# SSBSMINI_THROUGHHOLE.net
KiCad netlist of a schematic drawn in EAGLE
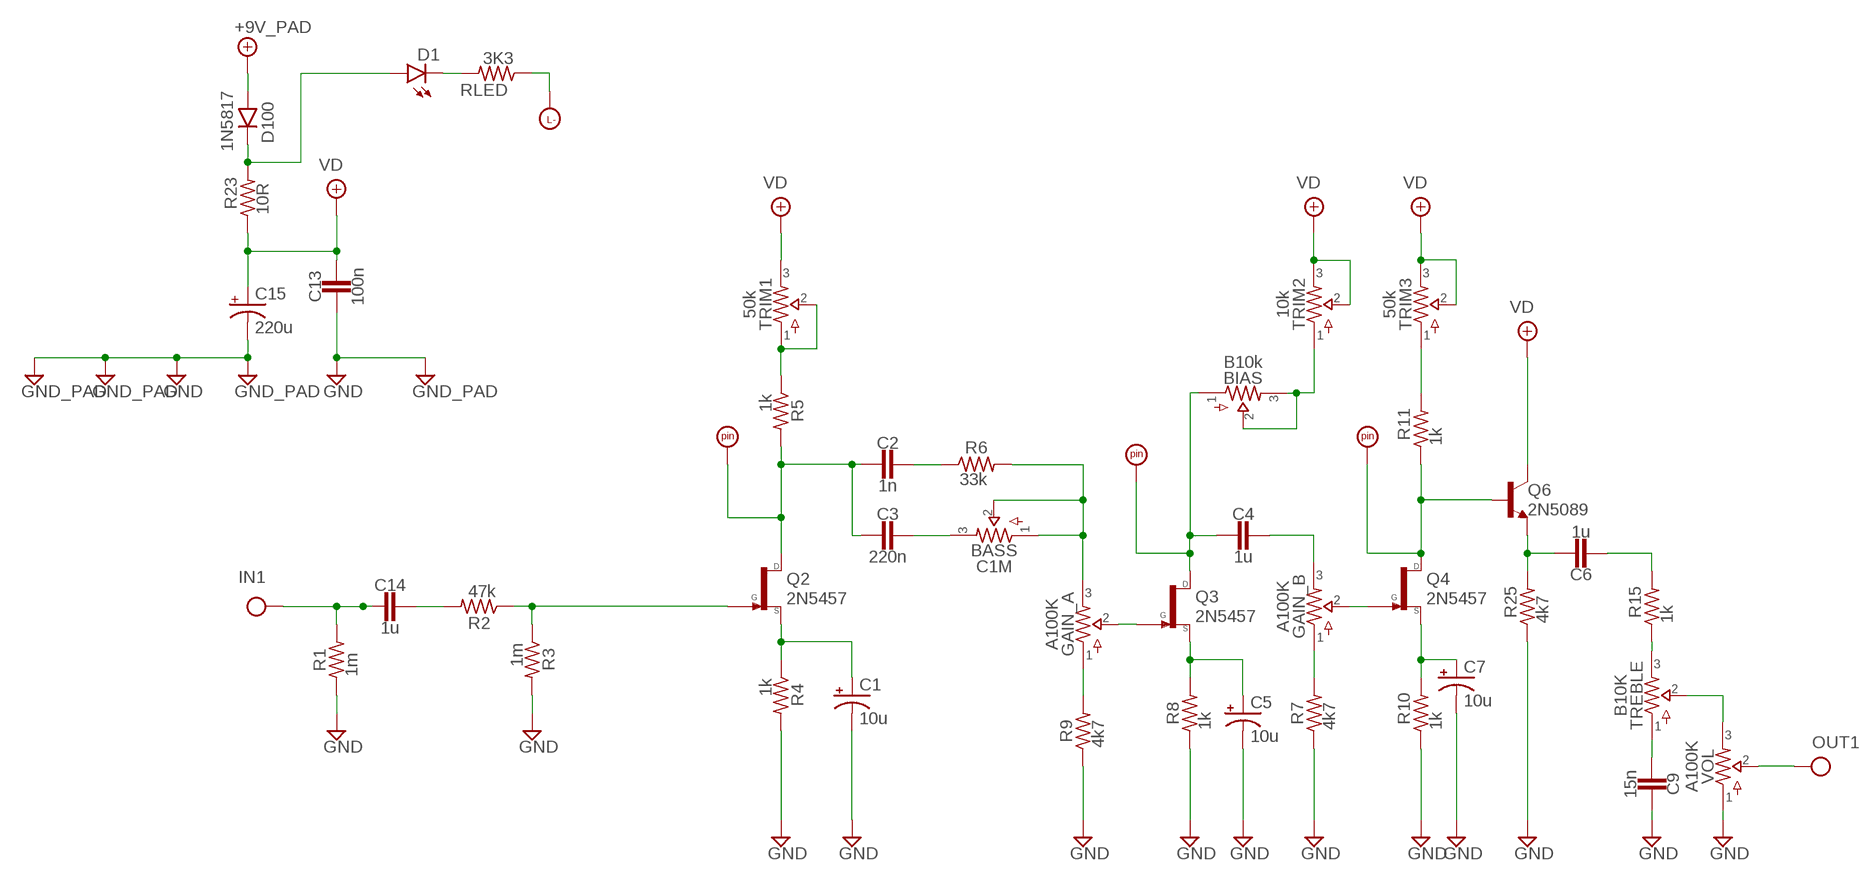
[diagram p0: schematic, sheet 1]

(export (version "E")
  (design (tool "Eeschema 10.0.6"))
  (components
    (comp (ref "BASS")
      (value "C1M")
      (footprint "eagle-import:16MM_B.MOUNT")
      (libsource (lib "eagle-import") (part "16MM.1"))
    )
    (comp (ref "BIAS")
      (value "B10k")
      (footprint "eagle-import:16MM_B.MOUNT")
      (libsource (lib "eagle-import") (part "16MM.1"))
    )
    (comp (ref "C1")
      (value "10u")
      (footprint "eagle-import:050_020_1")
      (libsource (lib "eagle-import") (part "0501"))
    )
    (comp (ref "C2")
      (value "1n")
      (footprint "eagle-import:0.2_.SML")
      (libsource (lib "eagle-import") (part "CAP.2"))
    )
    (comp (ref "C3")
      (value "220n")
      (footprint "eagle-import:0.2_.MED")
      (libsource (lib "eagle-import") (part "CAP.3"))
    )
    (comp (ref "C4")
      (value "1u")
      (footprint "eagle-import:0.2_.MED")
      (libsource (lib "eagle-import") (part "CAP.3"))
    )
    (comp (ref "C5")
      (value "10u")
      (footprint "eagle-import:050_020_1")
      (libsource (lib "eagle-import") (part "0501"))
    )
    (comp (ref "C6")
      (value "1u")
      (footprint "eagle-import:0.2_.MED")
      (libsource (lib "eagle-import") (part "CAP.3"))
    )
    (comp (ref "C7")
      (value "10u")
      (footprint "eagle-import:050_020_1")
      (libsource (lib "eagle-import") (part "0501"))
    )
    (comp (ref "C9")
      (value "15n")
      (footprint "eagle-import:0.2_.SML")
      (libsource (lib "eagle-import") (part "CAP.2"))
    )
    (comp (ref "C13")
      (value "100n")
      (footprint "eagle-import:0.2_.SML")
      (libsource (lib "eagle-import") (part "CAP.2"))
    )
    (comp (ref "C14")
      (value "1u")
      (footprint "eagle-import:0.2_.MED")
      (libsource (lib "eagle-import") (part "CAP.3"))
    )
    (comp (ref "C15")
      (value "220u")
      (footprint "eagle-import:063_025_2")
      (libsource (lib "eagle-import") (part "0632"))
    )
    (comp (ref "D1")
      (value "LED3MM")
      (footprint "eagle-import:LED3MM")
      (libsource (lib "eagle-import") (part "LED3MM"))
    )
    (comp (ref "D100")
      (value "1N5817")
      (footprint "eagle-import:DO35-3")
      (libsource (lib "eagle-import") (part "DO35.3"))
    )
    (comp (ref "GAIN")
      (value "A100K")
      (footprint "eagle-import:16MM_DUALGANG")
      (libsource (lib "eagle-import") (part "DUALGANG.2"))
    )
    (comp (ref "GND1")
      (value "GND_PAD")
      (footprint "eagle-import:SQUARE")
      (libsource (lib "eagle-import") (part "GND_PAD"))
    )
    (comp (ref "GND17")
      (value "GND_PAD")
      (footprint "eagle-import:SQUARE")
      (libsource (lib "eagle-import") (part "GND_PAD"))
    )
    (comp (ref "GND18")
      (value "GND_PAD")
      (footprint "eagle-import:SQUARE")
      (libsource (lib "eagle-import") (part "GND_PAD"))
    )
    (comp (ref "GND19")
      (value "GND_PAD")
      (footprint "eagle-import:SQUARE")
      (libsource (lib "eagle-import") (part "GND_PAD"))
    )
    (comp (ref "IN1")
      (value "IN")
      (footprint "eagle-import:SQUARE")
      (libsource (lib "eagle-import") (part "IN"))
    )
    (comp (ref "LED")
      (value "LED-")
      (footprint "eagle-import:SQUARE")
      (libsource (lib "eagle-import") (part "LED-"))
    )
    (comp (ref "OUT1")
      (value "OUT")
      (footprint "eagle-import:SQUARE")
      (libsource (lib "eagle-import") (part "OUT"))
    )
    (comp (ref "Q2")
      (value "2N5457")
      (footprint "eagle-import:TO92")
      (libsource (lib "eagle-import") (part "2N5457"))
    )
    (comp (ref "Q3")
      (value "2N5457")
      (footprint "eagle-import:TO92")
      (libsource (lib "eagle-import") (part "2N5457"))
    )
    (comp (ref "Q4")
      (value "2N5457")
      (footprint "eagle-import:TO92")
      (libsource (lib "eagle-import") (part "2N5457"))
    )
    (comp (ref "Q6")
      (value "2N5089")
      (footprint "eagle-import:TO92")
      (libsource (lib "eagle-import") (part "2N5088"))
    )
    (comp (ref "R1")
      (value "1m")
      (footprint "eagle-import:R0204_2")
      (libsource (lib "eagle-import") (part "RESISTORS.2"))
    )
    (comp (ref "R2")
      (value "47k")
      (footprint "eagle-import:R0204_2")
      (libsource (lib "eagle-import") (part "RESISTORS.2"))
    )
    (comp (ref "R3")
      (value "1m")
      (footprint "eagle-import:R0204_2")
      (libsource (lib "eagle-import") (part "RESISTORS.2"))
    )
    (comp (ref "R4")
      (value "1k")
      (footprint "eagle-import:R0204_2")
      (libsource (lib "eagle-import") (part "RESISTORS.2"))
    )
    (comp (ref "R5")
      (value "1k")
      (footprint "eagle-import:R0204_2")
      (libsource (lib "eagle-import") (part "RESISTORS.2"))
    )
    (comp (ref "R6")
      (value "33k")
      (footprint "eagle-import:R0204_2")
      (libsource (lib "eagle-import") (part "RESISTORS.2"))
    )
    (comp (ref "R7")
      (value "4k7")
      (footprint "eagle-import:R0204_2")
      (libsource (lib "eagle-import") (part "RESISTORS.2"))
    )
    (comp (ref "R8")
      (value "1k")
      (footprint "eagle-import:R0204_2")
      (libsource (lib "eagle-import") (part "RESISTORS.2"))
    )
    (comp (ref "R9")
      (value "4k7")
      (footprint "eagle-import:R0204_2")
      (libsource (lib "eagle-import") (part "RESISTORS.2"))
    )
    (comp (ref "R10")
      (value "1k")
      (footprint "eagle-import:R0204_2")
      (libsource (lib "eagle-import") (part "RESISTORS.2"))
    )
    (comp (ref "R11")
      (value "1k")
      (footprint "eagle-import:R0204_2")
      (libsource (lib "eagle-import") (part "RESISTORS.2"))
    )
    (comp (ref "R15")
      (value "1k")
      (footprint "eagle-import:R0204_2")
      (libsource (lib "eagle-import") (part "RESISTORS.2"))
    )
    (comp (ref "R23")
      (value "10R")
      (footprint "eagle-import:R0204_2")
      (libsource (lib "eagle-import") (part "RESISTORS.2"))
    )
    (comp (ref "R25")
      (value "4k7")
      (footprint "eagle-import:R0204_2")
      (libsource (lib "eagle-import") (part "RESISTORS.2"))
    )
    (comp (ref "RLED")
      (value "3K3")
      (footprint "eagle-import:R0204_2")
      (libsource (lib "eagle-import") (part "RESISTORS.2"))
    )
    (comp (ref "TREBLE")
      (value "B10K")
      (footprint "eagle-import:16MM_B.MOUNT")
      (libsource (lib "eagle-import") (part "16MM.1"))
    )
    (comp (ref "TRIM1")
      (value "50k")
      (footprint "eagle-import:TRIM1")
      (libsource (lib "eagle-import") (part "TRIMMER"))
    )
    (comp (ref "TRIM2")
      (value "10k")
      (footprint "eagle-import:TRIM1")
      (libsource (lib "eagle-import") (part "TRIMMER"))
    )
    (comp (ref "TRIM3")
      (value "50k")
      (footprint "eagle-import:TRIM1")
      (libsource (lib "eagle-import") (part "TRIMMER"))
    )
    (comp (ref "U$5")
      (value "PADS.RND_NL")
      (footprint "eagle-import:PAD2")
      (libsource (lib "eagle-import") (part "PADS.RND_NL"))
    )
    (comp (ref "U$6")
      (value "PADS.RND_NL")
      (footprint "eagle-import:PAD2")
      (libsource (lib "eagle-import") (part "PADS.RND_NL"))
    )
    (comp (ref "U$7")
      (value "PADS.RND_NL")
      (footprint "eagle-import:PAD2")
      (libsource (lib "eagle-import") (part "PADS.RND_NL"))
    )
    (comp (ref "V2")
      (value "+9V_PAD")
      (footprint "eagle-import:SQUARE")
      (libsource (lib "eagle-import") (part "+9V_PAD"))
    )
    (comp (ref "VOL")
      (value "A100K")
      (footprint "eagle-import:16MM_B.MOUNT")
      (libsource (lib "eagle-import") (part "16MM.1"))
    )
  )
  (nets
    (net (code "1") (name "+9V_PAD") (class "Default")
      (node (ref "D100") (pin "A") (pinfunction "A_A") (pintype "passive"))
      (node (ref "V2") (pin "1") (pinfunction "+9V_1") (pintype "power_in"))
    )
    (net (code "2") (name "GND") (class "Default")
      (node (ref "C1") (pin "-") (pinfunction "-_-") (pintype "passive"))
      (node (ref "C13") (pin "2") (pinfunction "2_2") (pintype "passive"))
      (node (ref "C15") (pin "-") (pinfunction "-_-") (pintype "passive"))
      (node (ref "C5") (pin "-") (pinfunction "-_-") (pintype "passive"))
      (node (ref "C7") (pin "-") (pinfunction "-_-") (pintype "passive"))
      (node (ref "C9") (pin "1") (pinfunction "1_1") (pintype "passive"))
      (node (ref "GND1") (pin "1") (pinfunction "GND_1") (pintype "power_in"))
      (node (ref "GND17") (pin "1") (pinfunction "GND_1") (pintype "power_in"))
      (node (ref "GND18") (pin "1") (pinfunction "GND_1") (pintype "power_in"))
      (node (ref "GND19") (pin "1") (pinfunction "GND_1") (pintype "power_in"))
      (node (ref "R1") (pin "1") (pinfunction "1_1") (pintype "passive"))
      (node (ref "R10") (pin "1") (pinfunction "1_1") (pintype "passive"))
      (node (ref "R25") (pin "1") (pinfunction "1_1") (pintype "passive"))
      (node (ref "R3") (pin "2") (pinfunction "2_2") (pintype "passive"))
      (node (ref "R4") (pin "2") (pinfunction "2_2") (pintype "passive"))
      (node (ref "R7") (pin "1") (pinfunction "1_1") (pintype "passive"))
      (node (ref "R8") (pin "1") (pinfunction "1_1") (pintype "passive"))
      (node (ref "R9") (pin "1") (pinfunction "1_1") (pintype "passive"))
      (node (ref "VOL") (pin "1") (pinfunction "1_1") (pintype "passive"))
    )
    (net (code "3") (name "IN") (class "Default")
      (node (ref "C14") (pin "2") (pinfunction "2_2") (pintype "passive"))
      (node (ref "IN1") (pin "1") (pinfunction "IN_1") (pintype "power_in"))
      (node (ref "R1") (pin "2") (pinfunction "2_2") (pintype "passive"))
    )
    (net (code "4") (name "Net-(BASS-Pad1)") (class "Default")
      (node (ref "BASS") (pin "1") (pinfunction "1_1") (pintype "passive"))
      (node (ref "BASS") (pin "2") (pinfunction "2_2") (pintype "passive"))
      (node (ref "GAIN") (pin "3") (pinfunction "3_3") (pintype "passive"))
      (node (ref "R6") (pin "2") (pinfunction "2_2") (pintype "passive"))
    )
    (net (code "5") (name "Net-(BASS-Pad3)") (class "Default")
      (node (ref "BASS") (pin "3") (pinfunction "3_3") (pintype "passive"))
      (node (ref "C3") (pin "1") (pinfunction "1_1") (pintype "passive"))
    )
    (net (code "6") (name "Net-(BIAS-Pad2)") (class "Default")
      (node (ref "BIAS") (pin "2") (pinfunction "2_2") (pintype "passive"))
      (node (ref "BIAS") (pin "3") (pinfunction "3_3") (pintype "passive"))
      (node (ref "TRIM2") (pin "1") (pinfunction "1_1") (pintype "passive"))
    )
    (net (code "7") (name "Net-(C2-Pad1)") (class "Default")
      (node (ref "C2") (pin "1") (pinfunction "1_1") (pintype "passive"))
      (node (ref "R6") (pin "1") (pinfunction "1_1") (pintype "passive"))
    )
    (net (code "8") (name "Net-(C6-Pad2)") (class "Default")
      (node (ref "C6") (pin "2") (pinfunction "2_2") (pintype "passive"))
      (node (ref "R15") (pin "2") (pinfunction "2_2") (pintype "passive"))
    )
    (net (code "9") (name "Net-(C9-Pad2)") (class "Default")
      (node (ref "C9") (pin "2") (pinfunction "2_2") (pintype "passive"))
      (node (ref "TREBLE") (pin "1") (pinfunction "1_1") (pintype "passive"))
    )
    (net (code "10") (name "Net-(C14-Pad1)") (class "Default")
      (node (ref "C14") (pin "1") (pinfunction "1_1") (pintype "passive"))
      (node (ref "R2") (pin "2") (pinfunction "2_2") (pintype "passive"))
    )
    (net (code "11") (name "Net-(D1-C)") (class "Default")
      (node (ref "D1") (pin "K") (pinfunction "C_K") (pintype "passive"))
      (node (ref "RLED") (pin "2") (pinfunction "2_2") (pintype "passive"))
    )
    (net (code "12") (name "Net-(D1-PadA)") (class "Default")
      (node (ref "D1") (pin "A") (pinfunction "A_A") (pintype "passive"))
      (node (ref "D100") (pin "C") (pinfunction "C_C") (pintype "passive"))
      (node (ref "R23") (pin "2") (pinfunction "2_2") (pintype "passive"))
    )
    (net (code "13") (name "Net-(GAIN-Pad1)") (class "Default")
      (node (ref "GAIN") (pin "1") (pinfunction "1_1") (pintype "passive"))
      (node (ref "R9") (pin "2") (pinfunction "2_2") (pintype "passive"))
    )
    (net (code "14") (name "Net-(GAINB-1)") (class "Default")
      (node (ref "GAIN") (pin "4") (pinfunction "1_4") (pintype "passive"))
      (node (ref "R7") (pin "2") (pinfunction "2_2") (pintype "passive"))
    )
    (net (code "15") (name "Net-(GAINB-2)") (class "Default")
      (node (ref "GAIN") (pin "5") (pinfunction "2_5") (pintype "passive"))
      (node (ref "Q4") (pin "3") (pinfunction "G_3") (pintype "passive"))
    )
    (net (code "16") (name "Net-(GAINB-3)") (class "Default")
      (node (ref "C4") (pin "1") (pinfunction "1_1") (pintype "passive"))
      (node (ref "GAIN") (pin "6") (pinfunction "3_6") (pintype "passive"))
    )
    (net (code "17") (name "Net-(LED-P$1)") (class "Default")
      (node (ref "LED") (pin "1") (pinfunction "P$1_1") (pintype "bidirectional"))
      (node (ref "RLED") (pin "1") (pinfunction "1_1") (pintype "passive"))
    )
    (net (code "18") (name "Net-(Q2-D)") (class "Default")
      (node (ref "C2") (pin "2") (pinfunction "2_2") (pintype "passive"))
      (node (ref "C3") (pin "2") (pinfunction "2_2") (pintype "passive"))
      (node (ref "Q2") (pin "1") (pinfunction "D_1") (pintype "passive"))
      (node (ref "R5") (pin "2") (pinfunction "2_2") (pintype "passive"))
      (node (ref "U$5") (pin "P$1") (pinfunction "P$1_P$1") (pintype "bidirectional"))
    )
    (net (code "19") (name "Net-(Q2-G)") (class "Default")
      (node (ref "Q2") (pin "3") (pinfunction "G_3") (pintype "passive"))
      (node (ref "R2") (pin "1") (pinfunction "1_1") (pintype "passive"))
      (node (ref "R3") (pin "1") (pinfunction "1_1") (pintype "passive"))
    )
    (net (code "20") (name "Net-(Q2-S)") (class "Default")
      (node (ref "C1") (pin "+") (pinfunction "+_+") (pintype "passive"))
      (node (ref "Q2") (pin "2") (pinfunction "S_2") (pintype "passive"))
      (node (ref "R4") (pin "1") (pinfunction "1_1") (pintype "passive"))
    )
    (net (code "21") (name "Net-(Q3-D)") (class "Default")
      (node (ref "BIAS") (pin "1") (pinfunction "1_1") (pintype "passive"))
      (node (ref "C4") (pin "2") (pinfunction "2_2") (pintype "passive"))
      (node (ref "Q3") (pin "1") (pinfunction "D_1") (pintype "passive"))
      (node (ref "U$6") (pin "P$1") (pinfunction "P$1_P$1") (pintype "bidirectional"))
    )
    (net (code "22") (name "Net-(Q3-G)") (class "Default")
      (node (ref "GAIN") (pin "2") (pinfunction "2_2") (pintype "passive"))
      (node (ref "Q3") (pin "3") (pinfunction "G_3") (pintype "passive"))
    )
    (net (code "23") (name "Net-(Q3-S)") (class "Default")
      (node (ref "C5") (pin "+") (pinfunction "+_+") (pintype "passive"))
      (node (ref "Q3") (pin "2") (pinfunction "S_2") (pintype "passive"))
      (node (ref "R8") (pin "2") (pinfunction "2_2") (pintype "passive"))
    )
    (net (code "24") (name "Net-(Q4-D)") (class "Default")
      (node (ref "Q4") (pin "1") (pinfunction "D_1") (pintype "passive"))
      (node (ref "Q6") (pin "2") (pinfunction "B_2") (pintype "passive"))
      (node (ref "R11") (pin "1") (pinfunction "1_1") (pintype "passive"))
      (node (ref "U$7") (pin "P$1") (pinfunction "P$1_P$1") (pintype "bidirectional"))
    )
    (net (code "25") (name "Net-(Q4-S)") (class "Default")
      (node (ref "C7") (pin "+") (pinfunction "+_+") (pintype "passive"))
      (node (ref "Q4") (pin "2") (pinfunction "S_2") (pintype "passive"))
      (node (ref "R10") (pin "2") (pinfunction "2_2") (pintype "passive"))
    )
    (net (code "26") (name "Net-(Q6-E)") (class "Default")
      (node (ref "C6") (pin "1") (pinfunction "1_1") (pintype "passive"))
      (node (ref "Q6") (pin "3") (pinfunction "E_3") (pintype "passive"))
      (node (ref "R25") (pin "2") (pinfunction "2_2") (pintype "passive"))
    )
    (net (code "27") (name "Net-(R5-Pad1)") (class "Default")
      (node (ref "R5") (pin "1") (pinfunction "1_1") (pintype "passive"))
      (node (ref "TRIM1") (pin "1") (pinfunction "1_1") (pintype "passive"))
      (node (ref "TRIM1") (pin "2") (pinfunction "2_2") (pintype "passive"))
    )
    (net (code "28") (name "Net-(R11-Pad2)") (class "Default")
      (node (ref "R11") (pin "2") (pinfunction "2_2") (pintype "passive"))
      (node (ref "TRIM3") (pin "1") (pinfunction "1_1") (pintype "passive"))
    )
    (net (code "29") (name "Net-(R15-Pad1)") (class "Default")
      (node (ref "R15") (pin "1") (pinfunction "1_1") (pintype "passive"))
      (node (ref "TREBLE") (pin "3") (pinfunction "3_3") (pintype "passive"))
    )
    (net (code "30") (name "Net-(TREBLE-Pad2)") (class "Default")
      (node (ref "TREBLE") (pin "2") (pinfunction "2_2") (pintype "passive"))
      (node (ref "VOL") (pin "3") (pinfunction "3_3") (pintype "passive"))
    )
    (net (code "31") (name "OUT") (class "Default")
      (node (ref "OUT1") (pin "1") (pinfunction "OUT_1") (pintype "power_in"))
      (node (ref "VOL") (pin "2") (pinfunction "2_2") (pintype "passive"))
    )
    (net (code "32") (name "VD") (class "Default")
      (node (ref "C13") (pin "1") (pinfunction "1_1") (pintype "passive"))
      (node (ref "C15") (pin "+") (pinfunction "+_+") (pintype "passive"))
      (node (ref "Q6") (pin "1") (pinfunction "C_1") (pintype "passive"))
      (node (ref "R23") (pin "1") (pinfunction "1_1") (pintype "passive"))
      (node (ref "TRIM1") (pin "3") (pinfunction "3_3") (pintype "passive"))
      (node (ref "TRIM2") (pin "2") (pinfunction "2_2") (pintype "passive"))
      (node (ref "TRIM2") (pin "3") (pinfunction "3_3") (pintype "passive"))
      (node (ref "TRIM3") (pin "2") (pinfunction "2_2") (pintype "passive"))
      (node (ref "TRIM3") (pin "3") (pinfunction "3_3") (pintype "passive"))
    )
  )
)
